# mcu.net
KiCad netlist of a schematic drawn in Altium Designer
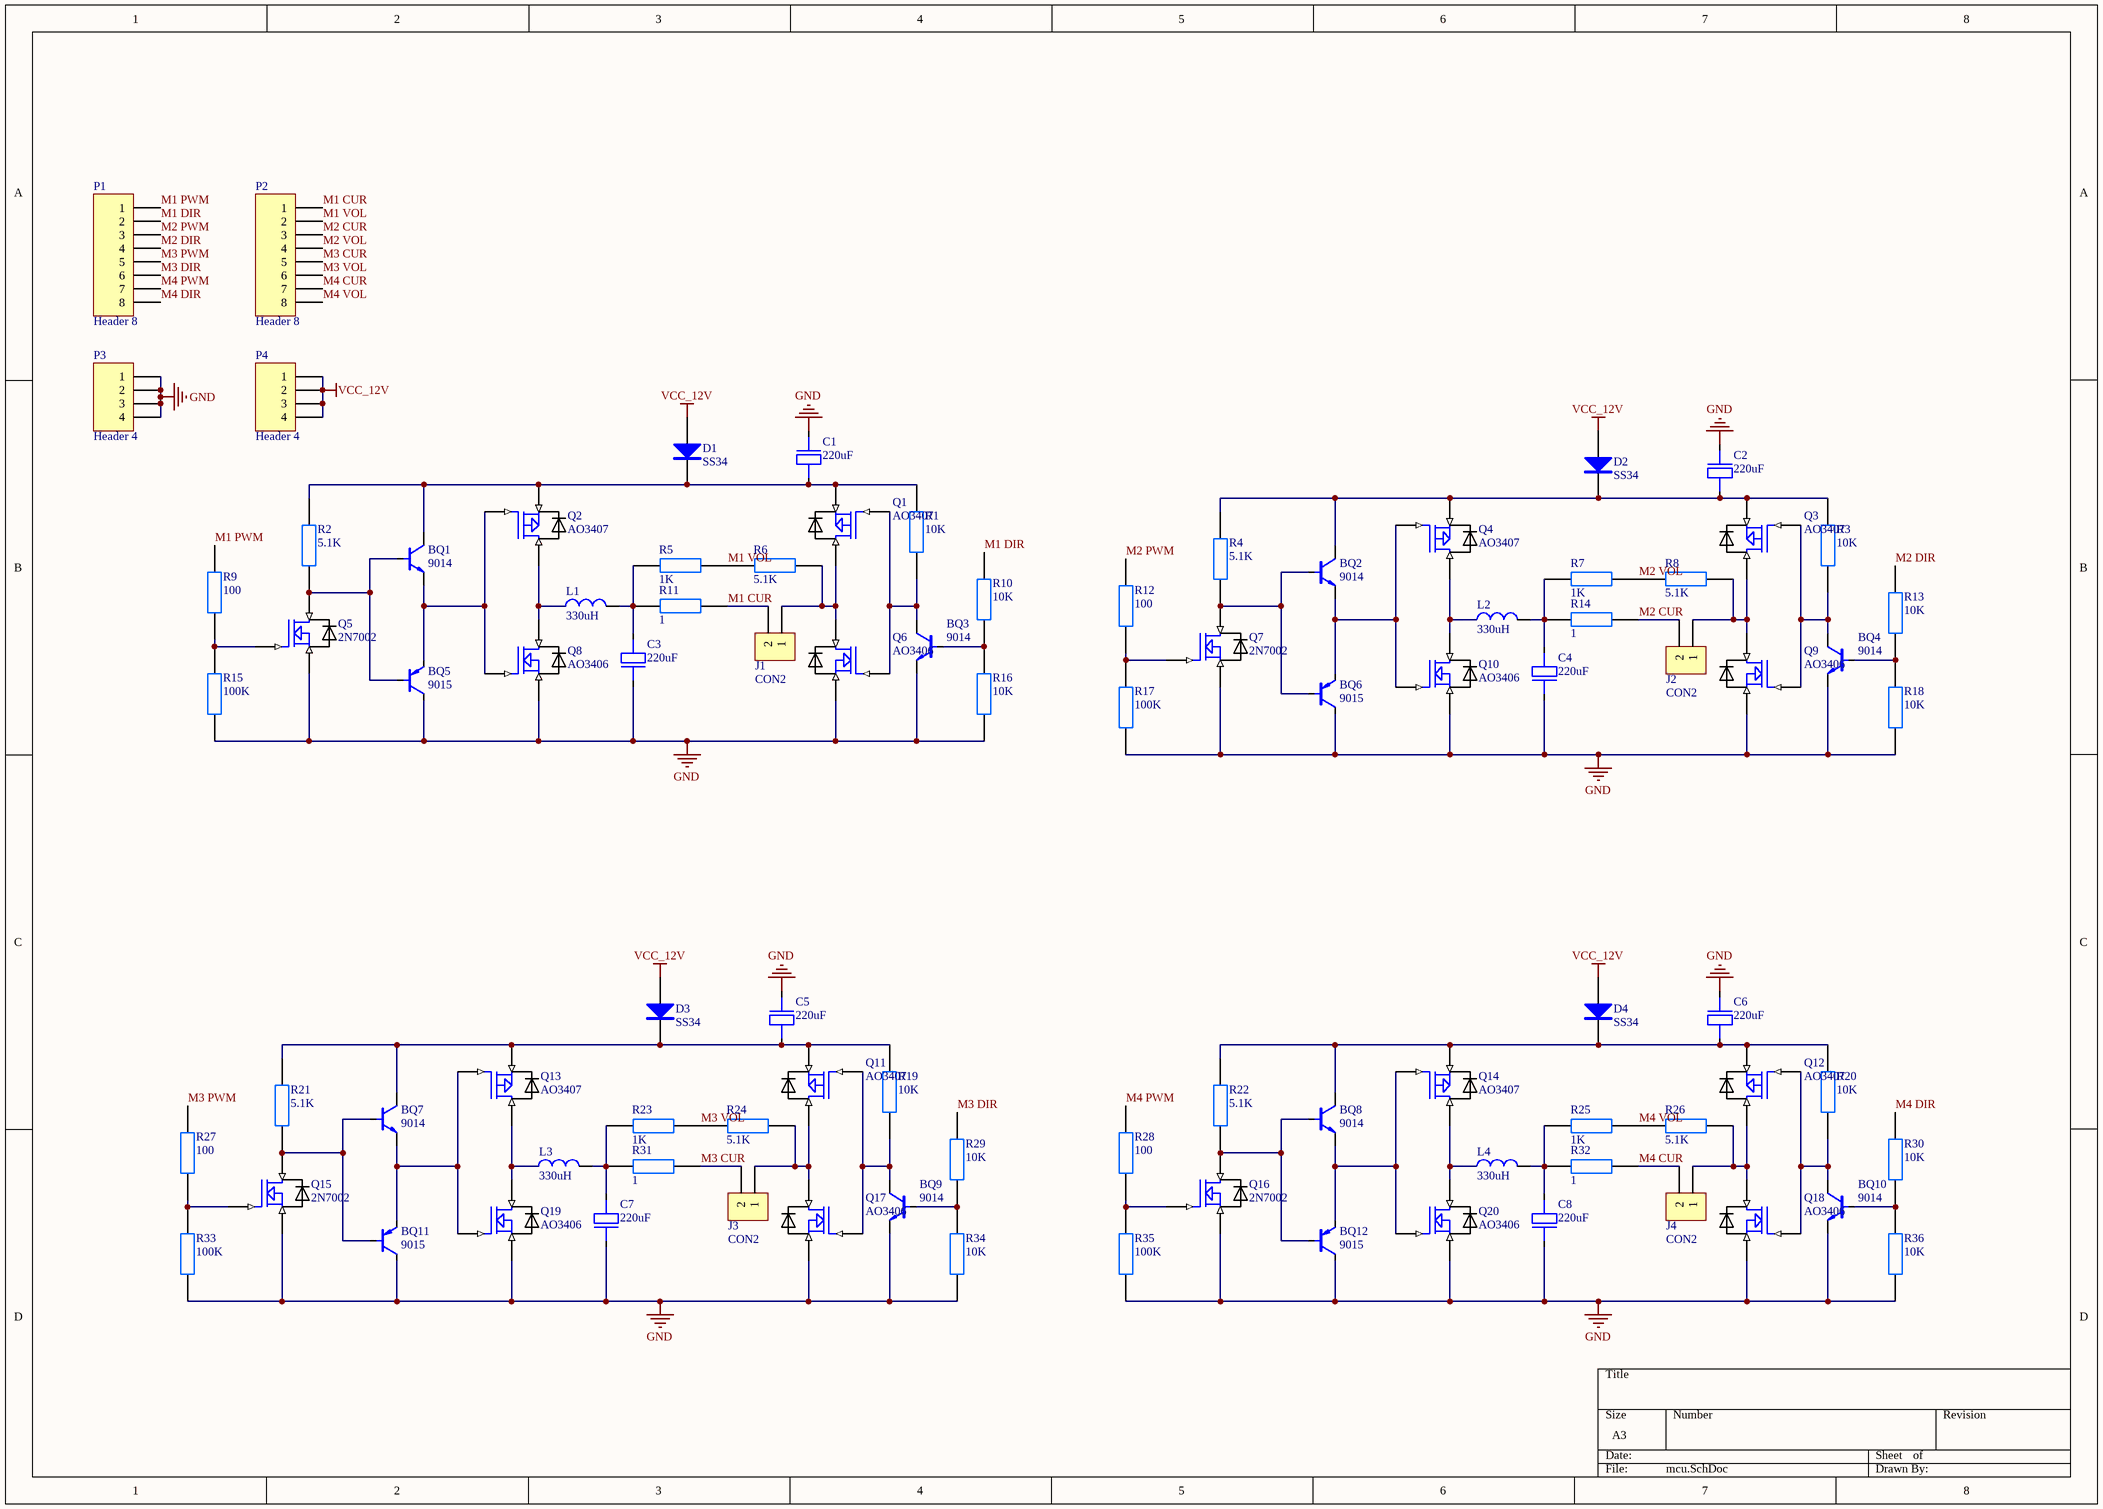
[diagram p0: mcu.SchDoc]

(export (version "E")
  (design (tool "Eeschema 10.0.6"))
  (components
    (comp (ref "BQ1")
      (value "9014")
      (footprint "SOT-23")
      (description "transistor")
      (libsource (lib "common") (part "9014"))
    )
    (comp (ref "BQ2")
      (value "9014")
      (footprint "SOT-23")
      (description "transistor")
      (libsource (lib "common") (part "9014"))
    )
    (comp (ref "BQ3")
      (value "9014")
      (footprint "SOT-23")
      (description "transistor")
      (libsource (lib "common") (part "9014"))
    )
    (comp (ref "BQ4")
      (value "9014")
      (footprint "SOT-23")
      (description "transistor")
      (libsource (lib "common") (part "9014"))
    )
    (comp (ref "BQ5")
      (value "9015")
      (footprint "SOT-23")
      (description "transistor")
      (libsource (lib "common") (part "9015"))
    )
    (comp (ref "BQ6")
      (value "9015")
      (footprint "SOT-23")
      (description "transistor")
      (libsource (lib "common") (part "9015"))
    )
    (comp (ref "BQ7")
      (value "9014")
      (footprint "SOT-23")
      (description "transistor")
      (libsource (lib "common") (part "9014"))
    )
    (comp (ref "BQ8")
      (value "9014")
      (footprint "SOT-23")
      (description "transistor")
      (libsource (lib "common") (part "9014"))
    )
    (comp (ref "BQ9")
      (value "9014")
      (footprint "SOT-23")
      (description "transistor")
      (libsource (lib "common") (part "9014"))
    )
    (comp (ref "BQ10")
      (value "9014")
      (footprint "SOT-23")
      (description "transistor")
      (libsource (lib "common") (part "9014"))
    )
    (comp (ref "BQ11")
      (value "9015")
      (footprint "SOT-23")
      (description "transistor")
      (libsource (lib "common") (part "9015"))
    )
    (comp (ref "BQ12")
      (value "9015")
      (footprint "SOT-23")
      (description "transistor")
      (libsource (lib "common") (part "9015"))
    )
    (comp (ref "C1") (value "220uF") (footprint "7443") (libsource (lib "common") (part "Electrolytic CAP")))
    (comp (ref "C2") (value "220uF") (footprint "7443") (libsource (lib "common") (part "Electrolytic CAP")))
    (comp (ref "C3") (value "220uF") (footprint "7443") (libsource (lib "common") (part "Electrolytic CAP")))
    (comp (ref "C4") (value "220uF") (footprint "7443") (libsource (lib "common") (part "Electrolytic CAP")))
    (comp (ref "C5") (value "220uF") (footprint "7443") (libsource (lib "common") (part "Electrolytic CAP")))
    (comp (ref "C6") (value "220uF") (footprint "7443") (libsource (lib "common") (part "Electrolytic CAP")))
    (comp (ref "C7") (value "220uF") (footprint "7443") (libsource (lib "common") (part "Electrolytic CAP")))
    (comp (ref "C8") (value "220uF") (footprint "7443") (libsource (lib "common") (part "Electrolytic CAP")))
    (comp (ref "D1")
      (value "SS34")
      (footprint "DO-241AC")
      (description "Diode")
      (libsource (lib "common") (part "SS14"))
    )
    (comp (ref "D2")
      (value "SS34")
      (footprint "DO-241AC")
      (description "Diode")
      (libsource (lib "common") (part "SS14"))
    )
    (comp (ref "D3")
      (value "SS34")
      (footprint "DO-241AC")
      (description "Diode")
      (libsource (lib "common") (part "SS14"))
    )
    (comp (ref "D4")
      (value "SS34")
      (footprint "DO-241AC")
      (description "Diode")
      (libsource (lib "common") (part "SS14"))
    )
    (comp (ref "J1") (value "CON2") (footprint "con2") (libsource (lib "common") (part "CON2")))
    (comp (ref "J2") (value "CON2") (footprint "con2") (libsource (lib "common") (part "CON2")))
    (comp (ref "J3") (value "CON2") (footprint "con2") (libsource (lib "common") (part "CON2")))
    (comp (ref "J4") (value "CON2") (footprint "con2") (libsource (lib "common") (part "CON2")))
    (comp (ref "L1") (value "330uH") (footprint "12x12") (libsource (lib "common") (part "Inductance")))
    (comp (ref "L2") (value "330uH") (footprint "12x12") (libsource (lib "common") (part "Inductance")))
    (comp (ref "L3") (value "330uH") (footprint "12x12") (libsource (lib "common") (part "Inductance")))
    (comp (ref "L4") (value "330uH") (footprint "12x12") (libsource (lib "common") (part "Inductance")))
    (comp (ref "P1")
      (value "Header 8")
      (footprint "sip8 N")
      (description "Header, 8-Pin")
      (fields (field (name "PUBLISHER") "Altium Limited"))
      (libsource (lib "Miscellaneous Connectors") (part "Header 8"))
    )
    (comp (ref "P2")
      (value "Header 8")
      (footprint "sip8 N")
      (description "Header, 8-Pin")
      (fields (field (name "PUBLISHER") "Altium Limited"))
      (libsource (lib "Miscellaneous Connectors") (part "Header 8"))
    )
    (comp (ref "P3")
      (value "Header 4")
      (footprint "sip4 N")
      (description "Header, 4-Pin")
      (fields (field (name "PUBLISHER") "Altium Limited"))
      (libsource (lib "Miscellaneous Connectors") (part "Header 4"))
    )
    (comp (ref "P4")
      (value "Header 4")
      (footprint "sip4 N")
      (description "Header, 4-Pin")
      (fields (field (name "PUBLISHER") "Altium Limited"))
      (libsource (lib "Miscellaneous Connectors") (part "Header 4"))
    )
    (comp (ref "Q1") (value "AO3407") (footprint "sot-23") (libsource (lib "common") (part "AO3407")))
    (comp (ref "Q2") (value "AO3407") (footprint "sot-23") (libsource (lib "common") (part "AO3407")))
    (comp (ref "Q3") (value "AO3407") (footprint "sot-23") (libsource (lib "common") (part "AO3407")))
    (comp (ref "Q4") (value "AO3407") (footprint "sot-23") (libsource (lib "common") (part "AO3407")))
    (comp (ref "Q5") (value "2N7002") (footprint "sot-23") (libsource (lib "common") (part "2N7002")))
    (comp (ref "Q6") (value "AO3406") (footprint "sot-23") (libsource (lib "common") (part "AO3406")))
    (comp (ref "Q7") (value "2N7002") (footprint "sot-23") (libsource (lib "common") (part "2N7002")))
    (comp (ref "Q8") (value "AO3406") (footprint "sot-23") (libsource (lib "common") (part "AO3406")))
    (comp (ref "Q9") (value "AO3406") (footprint "sot-23") (libsource (lib "common") (part "AO3406")))
    (comp (ref "Q10") (value "AO3406") (footprint "sot-23") (libsource (lib "common") (part "AO3406")))
    (comp (ref "Q11") (value "AO3407") (footprint "sot-23") (libsource (lib "common") (part "AO3407")))
    (comp (ref "Q12") (value "AO3407") (footprint "sot-23") (libsource (lib "common") (part "AO3407")))
    (comp (ref "Q13") (value "AO3407") (footprint "sot-23") (libsource (lib "common") (part "AO3407")))
    (comp (ref "Q14") (value "AO3407") (footprint "sot-23") (libsource (lib "common") (part "AO3407")))
    (comp (ref "Q15") (value "2N7002") (footprint "sot-23") (libsource (lib "common") (part "2N7002")))
    (comp (ref "Q16") (value "2N7002") (footprint "sot-23") (libsource (lib "common") (part "2N7002")))
    (comp (ref "Q17") (value "AO3406") (footprint "sot-23") (libsource (lib "common") (part "AO3406")))
    (comp (ref "Q18") (value "AO3406") (footprint "sot-23") (libsource (lib "common") (part "AO3406")))
    (comp (ref "Q19") (value "AO3406") (footprint "sot-23") (libsource (lib "common") (part "AO3406")))
    (comp (ref "Q20") (value "AO3406") (footprint "sot-23") (libsource (lib "common") (part "AO3406")))
    (comp (ref "R1")
      (value "10K")
      (footprint "0805")
      (description "RES")
      (libsource (lib "common") (part "RES"))
    )
    (comp (ref "R2")
      (value "5.1K")
      (footprint "0805")
      (description "RES")
      (libsource (lib "common") (part "RES"))
    )
    (comp (ref "R3")
      (value "10K")
      (footprint "0805")
      (description "RES")
      (libsource (lib "common") (part "RES"))
    )
    (comp (ref "R4")
      (value "5.1K")
      (footprint "0805")
      (description "RES")
      (libsource (lib "common") (part "RES"))
    )
    (comp (ref "R5")
      (value "1K")
      (footprint "0805")
      (description "RES")
      (libsource (lib "common") (part "RES"))
    )
    (comp (ref "R6")
      (value "5.1K")
      (footprint "0805")
      (description "RES")
      (libsource (lib "common") (part "RES"))
    )
    (comp (ref "R7")
      (value "1K")
      (footprint "0805")
      (description "RES")
      (libsource (lib "common") (part "RES"))
    )
    (comp (ref "R8")
      (value "5.1K")
      (footprint "0805")
      (description "RES")
      (libsource (lib "common") (part "RES"))
    )
    (comp (ref "R9")
      (value "100")
      (footprint "0805")
      (description "RES")
      (libsource (lib "common") (part "RES"))
    )
    (comp (ref "R10")
      (value "10K")
      (footprint "0805")
      (description "RES")
      (libsource (lib "common") (part "RES"))
    )
    (comp (ref "R11")
      (value "1")
      (footprint "2512")
      (description "RES")
      (libsource (lib "common") (part "RES"))
    )
    (comp (ref "R12")
      (value "100")
      (footprint "0805")
      (description "RES")
      (libsource (lib "common") (part "RES"))
    )
    (comp (ref "R13")
      (value "10K")
      (footprint "0805")
      (description "RES")
      (libsource (lib "common") (part "RES"))
    )
    (comp (ref "R14")
      (value "1")
      (footprint "2512")
      (description "RES")
      (libsource (lib "common") (part "RES"))
    )
    (comp (ref "R15")
      (value "100K")
      (footprint "0805")
      (description "RES")
      (libsource (lib "common") (part "RES"))
    )
    (comp (ref "R16")
      (value "10K")
      (footprint "0805")
      (description "RES")
      (libsource (lib "common") (part "RES"))
    )
    (comp (ref "R17")
      (value "100K")
      (footprint "0805")
      (description "RES")
      (libsource (lib "common") (part "RES"))
    )
    (comp (ref "R18")
      (value "10K")
      (footprint "0805")
      (description "RES")
      (libsource (lib "common") (part "RES"))
    )
    (comp (ref "R19")
      (value "10K")
      (footprint "0805")
      (description "RES")
      (libsource (lib "common") (part "RES"))
    )
    (comp (ref "R20")
      (value "10K")
      (footprint "0805")
      (description "RES")
      (libsource (lib "common") (part "RES"))
    )
    (comp (ref "R21")
      (value "5.1K")
      (footprint "0805")
      (description "RES")
      (libsource (lib "common") (part "RES"))
    )
    (comp (ref "R22")
      (value "5.1K")
      (footprint "0805")
      (description "RES")
      (libsource (lib "common") (part "RES"))
    )
    (comp (ref "R23")
      (value "1K")
      (footprint "0805")
      (description "RES")
      (libsource (lib "common") (part "RES"))
    )
    (comp (ref "R24")
      (value "5.1K")
      (footprint "0805")
      (description "RES")
      (libsource (lib "common") (part "RES"))
    )
    (comp (ref "R25")
      (value "1K")
      (footprint "0805")
      (description "RES")
      (libsource (lib "common") (part "RES"))
    )
    (comp (ref "R26")
      (value "5.1K")
      (footprint "0805")
      (description "RES")
      (libsource (lib "common") (part "RES"))
    )
    (comp (ref "R27")
      (value "100")
      (footprint "0805")
      (description "RES")
      (libsource (lib "common") (part "RES"))
    )
    (comp (ref "R28")
      (value "100")
      (footprint "0805")
      (description "RES")
      (libsource (lib "common") (part "RES"))
    )
    (comp (ref "R29")
      (value "10K")
      (footprint "0805")
      (description "RES")
      (libsource (lib "common") (part "RES"))
    )
    (comp (ref "R30")
      (value "10K")
      (footprint "0805")
      (description "RES")
      (libsource (lib "common") (part "RES"))
    )
    (comp (ref "R31")
      (value "1")
      (footprint "2512")
      (description "RES")
      (libsource (lib "common") (part "RES"))
    )
    (comp (ref "R32")
      (value "1")
      (footprint "2512")
      (description "RES")
      (libsource (lib "common") (part "RES"))
    )
    (comp (ref "R33")
      (value "100K")
      (footprint "0805")
      (description "RES")
      (libsource (lib "common") (part "RES"))
    )
    (comp (ref "R34")
      (value "10K")
      (footprint "0805")
      (description "RES")
      (libsource (lib "common") (part "RES"))
    )
    (comp (ref "R35")
      (value "100K")
      (footprint "0805")
      (description "RES")
      (libsource (lib "common") (part "RES"))
    )
    (comp (ref "R36")
      (value "10K")
      (footprint "0805")
      (description "RES")
      (libsource (lib "common") (part "RES"))
    )
  )
  (nets
    (net (code "1") (name "/M1 CUR") (class "Default")
      (node (ref "J1") (pin "2") (pinfunction "2_2") (pintype "passive"))
      (node (ref "P2") (pin "1") (pinfunction "1_1") (pintype "passive"))
      (node (ref "R11") (pin "2") (pinfunction "2_2") (pintype "passive"))
    )
    (net (code "2") (name "/M1 DIR") (class "Default")
      (node (ref "P1") (pin "2") (pinfunction "2_2") (pintype "passive"))
      (node (ref "R10") (pin "2") (pinfunction "2_2") (pintype "passive"))
    )
    (net (code "3") (name "/M1 PWM") (class "Default")
      (node (ref "P1") (pin "1") (pinfunction "1_1") (pintype "passive"))
      (node (ref "R9") (pin "2") (pinfunction "2_2") (pintype "passive"))
    )
    (net (code "4") (name "/M1 VOL") (class "Default")
      (node (ref "P2") (pin "2") (pinfunction "2_2") (pintype "passive"))
      (node (ref "R5") (pin "2") (pinfunction "2_2") (pintype "passive"))
      (node (ref "R6") (pin "1") (pinfunction "1_1") (pintype "passive"))
    )
    (net (code "5") (name "/M2 CUR") (class "Default")
      (node (ref "J2") (pin "2") (pinfunction "2_2") (pintype "passive"))
      (node (ref "P2") (pin "3") (pinfunction "3_3") (pintype "passive"))
      (node (ref "R14") (pin "2") (pinfunction "2_2") (pintype "passive"))
    )
    (net (code "6") (name "/M2 DIR") (class "Default")
      (node (ref "P1") (pin "4") (pinfunction "4_4") (pintype "passive"))
      (node (ref "R13") (pin "2") (pinfunction "2_2") (pintype "passive"))
    )
    (net (code "7") (name "/M2 PWM") (class "Default")
      (node (ref "P1") (pin "3") (pinfunction "3_3") (pintype "passive"))
      (node (ref "R12") (pin "2") (pinfunction "2_2") (pintype "passive"))
    )
    (net (code "8") (name "/M2 VOL") (class "Default")
      (node (ref "P2") (pin "4") (pinfunction "4_4") (pintype "passive"))
      (node (ref "R7") (pin "2") (pinfunction "2_2") (pintype "passive"))
      (node (ref "R8") (pin "1") (pinfunction "1_1") (pintype "passive"))
    )
    (net (code "9") (name "/M3 CUR") (class "Default")
      (node (ref "J3") (pin "2") (pinfunction "2_2") (pintype "passive"))
      (node (ref "P2") (pin "5") (pinfunction "5_5") (pintype "passive"))
      (node (ref "R31") (pin "2") (pinfunction "2_2") (pintype "passive"))
    )
    (net (code "10") (name "/M3 DIR") (class "Default")
      (node (ref "P1") (pin "6") (pinfunction "6_6") (pintype "passive"))
      (node (ref "R29") (pin "2") (pinfunction "2_2") (pintype "passive"))
    )
    (net (code "11") (name "/M3 PWM") (class "Default")
      (node (ref "P1") (pin "5") (pinfunction "5_5") (pintype "passive"))
      (node (ref "R27") (pin "2") (pinfunction "2_2") (pintype "passive"))
    )
    (net (code "12") (name "/M3 VOL") (class "Default")
      (node (ref "P2") (pin "6") (pinfunction "6_6") (pintype "passive"))
      (node (ref "R23") (pin "2") (pinfunction "2_2") (pintype "passive"))
      (node (ref "R24") (pin "1") (pinfunction "1_1") (pintype "passive"))
    )
    (net (code "13") (name "/M4 CUR") (class "Default")
      (node (ref "J4") (pin "2") (pinfunction "2_2") (pintype "passive"))
      (node (ref "P2") (pin "7") (pinfunction "7_7") (pintype "passive"))
      (node (ref "R32") (pin "2") (pinfunction "2_2") (pintype "passive"))
    )
    (net (code "14") (name "/M4 DIR") (class "Default")
      (node (ref "P1") (pin "8") (pinfunction "8_8") (pintype "passive"))
      (node (ref "R30") (pin "2") (pinfunction "2_2") (pintype "passive"))
    )
    (net (code "15") (name "/M4 PWM") (class "Default")
      (node (ref "P1") (pin "7") (pinfunction "7_7") (pintype "passive"))
      (node (ref "R28") (pin "2") (pinfunction "2_2") (pintype "passive"))
    )
    (net (code "16") (name "/M4 VOL") (class "Default")
      (node (ref "P2") (pin "8") (pinfunction "8_8") (pintype "passive"))
      (node (ref "R25") (pin "2") (pinfunction "2_2") (pintype "passive"))
      (node (ref "R26") (pin "1") (pinfunction "1_1") (pintype "passive"))
    )
    (net (code "17") (name "GND") (class "Default")
      (node (ref "BQ10") (pin "e") (pinfunction "e_e") (pintype "passive"))
      (node (ref "BQ11") (pin "c") (pinfunction "c_c") (pintype "passive"))
      (node (ref "BQ12") (pin "c") (pinfunction "c_c") (pintype "passive"))
      (node (ref "BQ3") (pin "e") (pinfunction "e_e") (pintype "passive"))
      (node (ref "BQ4") (pin "e") (pinfunction "e_e") (pintype "passive"))
      (node (ref "BQ5") (pin "c") (pinfunction "c_c") (pintype "passive"))
      (node (ref "BQ6") (pin "c") (pinfunction "c_c") (pintype "passive"))
      (node (ref "BQ9") (pin "e") (pinfunction "e_e") (pintype "passive"))
      (node (ref "C1") (pin "2") (pinfunction "2_2") (pintype "passive"))
      (node (ref "C2") (pin "2") (pinfunction "2_2") (pintype "passive"))
      (node (ref "C3") (pin "2") (pinfunction "2_2") (pintype "passive"))
      (node (ref "C4") (pin "2") (pinfunction "2_2") (pintype "passive"))
      (node (ref "C5") (pin "2") (pinfunction "2_2") (pintype "passive"))
      (node (ref "C6") (pin "2") (pinfunction "2_2") (pintype "passive"))
      (node (ref "C7") (pin "2") (pinfunction "2_2") (pintype "passive"))
      (node (ref "C8") (pin "2") (pinfunction "2_2") (pintype "passive"))
      (node (ref "P3") (pin "1") (pinfunction "1_1") (pintype "passive"))
      (node (ref "P3") (pin "2") (pinfunction "2_2") (pintype "passive"))
      (node (ref "P3") (pin "3") (pinfunction "3_3") (pintype "passive"))
      (node (ref "P3") (pin "4") (pinfunction "4_4") (pintype "passive"))
      (node (ref "Q10") (pin "3") (pinfunction "S_3") (pintype "input"))
      (node (ref "Q15") (pin "3") (pinfunction "S_3") (pintype "input"))
      (node (ref "Q16") (pin "3") (pinfunction "S_3") (pintype "input"))
      (node (ref "Q17") (pin "3") (pinfunction "S_3") (pintype "input"))
      (node (ref "Q18") (pin "3") (pinfunction "S_3") (pintype "input"))
      (node (ref "Q19") (pin "3") (pinfunction "S_3") (pintype "input"))
      (node (ref "Q20") (pin "3") (pinfunction "S_3") (pintype "input"))
      (node (ref "Q5") (pin "3") (pinfunction "S_3") (pintype "input"))
      (node (ref "Q6") (pin "3") (pinfunction "S_3") (pintype "input"))
      (node (ref "Q7") (pin "3") (pinfunction "S_3") (pintype "input"))
      (node (ref "Q8") (pin "3") (pinfunction "S_3") (pintype "input"))
      (node (ref "Q9") (pin "3") (pinfunction "S_3") (pintype "input"))
      (node (ref "R15") (pin "1") (pinfunction "1_1") (pintype "passive"))
      (node (ref "R16") (pin "1") (pinfunction "1_1") (pintype "passive"))
      (node (ref "R17") (pin "1") (pinfunction "1_1") (pintype "passive"))
      (node (ref "R18") (pin "1") (pinfunction "1_1") (pintype "passive"))
      (node (ref "R33") (pin "1") (pinfunction "1_1") (pintype "passive"))
      (node (ref "R34") (pin "1") (pinfunction "1_1") (pintype "passive"))
      (node (ref "R35") (pin "1") (pinfunction "1_1") (pintype "passive"))
      (node (ref "R36") (pin "1") (pinfunction "1_1") (pintype "passive"))
    )
    (net (code "18") (name "Net-(BQ3-Padb)") (class "Default")
      (node (ref "BQ3") (pin "b") (pinfunction "b_b") (pintype "passive"))
      (node (ref "R10") (pin "1") (pinfunction "1_1") (pintype "passive"))
      (node (ref "R16") (pin "2") (pinfunction "2_2") (pintype "passive"))
    )
    (net (code "19") (name "Net-(BQ4-Padb)") (class "Default")
      (node (ref "BQ4") (pin "b") (pinfunction "b_b") (pintype "passive"))
      (node (ref "R13") (pin "1") (pinfunction "1_1") (pintype "passive"))
      (node (ref "R18") (pin "2") (pinfunction "2_2") (pintype "passive"))
    )
    (net (code "20") (name "Net-(BQ9-Padb)") (class "Default")
      (node (ref "BQ9") (pin "b") (pinfunction "b_b") (pintype "passive"))
      (node (ref "R29") (pin "1") (pinfunction "1_1") (pintype "passive"))
      (node (ref "R34") (pin "2") (pinfunction "2_2") (pintype "passive"))
    )
    (net (code "21") (name "Net-(BQ10-Padb)") (class "Default")
      (node (ref "BQ10") (pin "b") (pinfunction "b_b") (pintype "passive"))
      (node (ref "R30") (pin "1") (pinfunction "1_1") (pintype "passive"))
      (node (ref "R36") (pin "2") (pinfunction "2_2") (pintype "passive"))
    )
    (net (code "22") (name "Net-(C3-Pad1)") (class "Default")
      (node (ref "C3") (pin "1") (pinfunction "1_1") (pintype "passive"))
      (node (ref "L1") (pin "1") (pinfunction "1_1") (pintype "passive"))
      (node (ref "R11") (pin "1") (pinfunction "1_1") (pintype "passive"))
      (node (ref "R5") (pin "1") (pinfunction "1_1") (pintype "passive"))
    )
    (net (code "23") (name "Net-(C4-Pad1)") (class "Default")
      (node (ref "C4") (pin "1") (pinfunction "1_1") (pintype "passive"))
      (node (ref "L2") (pin "1") (pinfunction "1_1") (pintype "passive"))
      (node (ref "R14") (pin "1") (pinfunction "1_1") (pintype "passive"))
      (node (ref "R7") (pin "1") (pinfunction "1_1") (pintype "passive"))
    )
    (net (code "24") (name "Net-(C7-Pad1)") (class "Default")
      (node (ref "C7") (pin "1") (pinfunction "1_1") (pintype "passive"))
      (node (ref "L3") (pin "1") (pinfunction "1_1") (pintype "passive"))
      (node (ref "R23") (pin "1") (pinfunction "1_1") (pintype "passive"))
      (node (ref "R31") (pin "1") (pinfunction "1_1") (pintype "passive"))
    )
    (net (code "25") (name "Net-(C8-Pad1)") (class "Default")
      (node (ref "C8") (pin "1") (pinfunction "1_1") (pintype "passive"))
      (node (ref "L4") (pin "1") (pinfunction "1_1") (pintype "passive"))
      (node (ref "R25") (pin "1") (pinfunction "1_1") (pintype "passive"))
      (node (ref "R32") (pin "1") (pinfunction "1_1") (pintype "passive"))
    )
    (net (code "26") (name "Net-(D1-K)") (class "Default")
      (node (ref "BQ1") (pin "c") (pinfunction "c_c") (pintype "passive"))
      (node (ref "C1") (pin "1") (pinfunction "1_1") (pintype "passive"))
      (node (ref "D1") (pin "2") (pinfunction "K_2") (pintype "passive"))
      (node (ref "Q1") (pin "3") (pinfunction "S_3") (pintype "input"))
      (node (ref "Q2") (pin "3") (pinfunction "S_3") (pintype "input"))
      (node (ref "R1") (pin "2") (pinfunction "2_2") (pintype "passive"))
      (node (ref "R2") (pin "2") (pinfunction "2_2") (pintype "passive"))
    )
    (net (code "27") (name "Net-(D2-K)") (class "Default")
      (node (ref "BQ2") (pin "c") (pinfunction "c_c") (pintype "passive"))
      (node (ref "C2") (pin "1") (pinfunction "1_1") (pintype "passive"))
      (node (ref "D2") (pin "2") (pinfunction "K_2") (pintype "passive"))
      (node (ref "Q3") (pin "3") (pinfunction "S_3") (pintype "input"))
      (node (ref "Q4") (pin "3") (pinfunction "S_3") (pintype "input"))
      (node (ref "R3") (pin "2") (pinfunction "2_2") (pintype "passive"))
      (node (ref "R4") (pin "2") (pinfunction "2_2") (pintype "passive"))
    )
    (net (code "28") (name "Net-(D3-K)") (class "Default")
      (node (ref "BQ7") (pin "c") (pinfunction "c_c") (pintype "passive"))
      (node (ref "C5") (pin "1") (pinfunction "1_1") (pintype "passive"))
      (node (ref "D3") (pin "2") (pinfunction "K_2") (pintype "passive"))
      (node (ref "Q11") (pin "3") (pinfunction "S_3") (pintype "input"))
      (node (ref "Q13") (pin "3") (pinfunction "S_3") (pintype "input"))
      (node (ref "R19") (pin "2") (pinfunction "2_2") (pintype "passive"))
      (node (ref "R21") (pin "2") (pinfunction "2_2") (pintype "passive"))
    )
    (net (code "29") (name "Net-(D4-K)") (class "Default")
      (node (ref "BQ8") (pin "c") (pinfunction "c_c") (pintype "passive"))
      (node (ref "C6") (pin "1") (pinfunction "1_1") (pintype "passive"))
      (node (ref "D4") (pin "2") (pinfunction "K_2") (pintype "passive"))
      (node (ref "Q12") (pin "3") (pinfunction "S_3") (pintype "input"))
      (node (ref "Q14") (pin "3") (pinfunction "S_3") (pintype "input"))
      (node (ref "R20") (pin "2") (pinfunction "2_2") (pintype "passive"))
      (node (ref "R22") (pin "2") (pinfunction "2_2") (pintype "passive"))
    )
    (net (code "30") (name "Net-(Q1-D)") (class "Default")
      (node (ref "J1") (pin "1") (pinfunction "1_1") (pintype "passive"))
      (node (ref "Q1") (pin "2") (pinfunction "D_2") (pintype "input"))
      (node (ref "Q6") (pin "2") (pinfunction "D_2") (pintype "input"))
      (node (ref "R6") (pin "2") (pinfunction "2_2") (pintype "passive"))
    )
    (net (code "31") (name "Net-(Q1-G)") (class "Default")
      (node (ref "BQ3") (pin "c") (pinfunction "c_c") (pintype "passive"))
      (node (ref "Q1") (pin "1") (pinfunction "G_1") (pintype "input"))
      (node (ref "Q6") (pin "1") (pinfunction "G_1") (pintype "input"))
      (node (ref "R1") (pin "1") (pinfunction "1_1") (pintype "passive"))
    )
    (net (code "32") (name "Net-(Q2-D)") (class "Default")
      (node (ref "L1") (pin "2") (pinfunction "2_2") (pintype "passive"))
      (node (ref "Q2") (pin "2") (pinfunction "D_2") (pintype "input"))
      (node (ref "Q8") (pin "2") (pinfunction "D_2") (pintype "input"))
    )
    (net (code "33") (name "Net-(Q2-G)") (class "Default")
      (node (ref "BQ1") (pin "e") (pinfunction "e_e") (pintype "passive"))
      (node (ref "BQ5") (pin "e") (pinfunction "e_e") (pintype "passive"))
      (node (ref "Q2") (pin "1") (pinfunction "G_1") (pintype "input"))
      (node (ref "Q8") (pin "1") (pinfunction "G_1") (pintype "input"))
    )
    (net (code "34") (name "Net-(Q3-D)") (class "Default")
      (node (ref "J2") (pin "1") (pinfunction "1_1") (pintype "passive"))
      (node (ref "Q3") (pin "2") (pinfunction "D_2") (pintype "input"))
      (node (ref "Q9") (pin "2") (pinfunction "D_2") (pintype "input"))
      (node (ref "R8") (pin "2") (pinfunction "2_2") (pintype "passive"))
    )
    (net (code "35") (name "Net-(Q3-G)") (class "Default")
      (node (ref "BQ4") (pin "c") (pinfunction "c_c") (pintype "passive"))
      (node (ref "Q3") (pin "1") (pinfunction "G_1") (pintype "input"))
      (node (ref "Q9") (pin "1") (pinfunction "G_1") (pintype "input"))
      (node (ref "R3") (pin "1") (pinfunction "1_1") (pintype "passive"))
    )
    (net (code "36") (name "Net-(Q5-D)") (class "Default")
      (node (ref "BQ1") (pin "b") (pinfunction "b_b") (pintype "passive"))
      (node (ref "BQ5") (pin "b") (pinfunction "b_b") (pintype "passive"))
      (node (ref "Q5") (pin "2") (pinfunction "D_2") (pintype "input"))
      (node (ref "R2") (pin "1") (pinfunction "1_1") (pintype "passive"))
    )
    (net (code "37") (name "Net-(Q5-G)") (class "Default")
      (node (ref "Q5") (pin "1") (pinfunction "G_1") (pintype "input"))
      (node (ref "R15") (pin "2") (pinfunction "2_2") (pintype "passive"))
      (node (ref "R9") (pin "1") (pinfunction "1_1") (pintype "passive"))
    )
    (net (code "38") (name "Net-(Q7-D)") (class "Default")
      (node (ref "BQ2") (pin "b") (pinfunction "b_b") (pintype "passive"))
      (node (ref "BQ6") (pin "b") (pinfunction "b_b") (pintype "passive"))
      (node (ref "Q7") (pin "2") (pinfunction "D_2") (pintype "input"))
      (node (ref "R4") (pin "1") (pinfunction "1_1") (pintype "passive"))
    )
    (net (code "39") (name "Net-(Q7-G)") (class "Default")
      (node (ref "Q7") (pin "1") (pinfunction "G_1") (pintype "input"))
      (node (ref "R12") (pin "1") (pinfunction "1_1") (pintype "passive"))
      (node (ref "R17") (pin "2") (pinfunction "2_2") (pintype "passive"))
    )
    (net (code "40") (name "Net-(Q10-D)") (class "Default")
      (node (ref "L2") (pin "2") (pinfunction "2_2") (pintype "passive"))
      (node (ref "Q10") (pin "2") (pinfunction "D_2") (pintype "input"))
      (node (ref "Q4") (pin "2") (pinfunction "D_2") (pintype "input"))
    )
    (net (code "41") (name "Net-(Q10-G)") (class "Default")
      (node (ref "BQ2") (pin "e") (pinfunction "e_e") (pintype "passive"))
      (node (ref "BQ6") (pin "e") (pinfunction "e_e") (pintype "passive"))
      (node (ref "Q10") (pin "1") (pinfunction "G_1") (pintype "input"))
      (node (ref "Q4") (pin "1") (pinfunction "G_1") (pintype "input"))
    )
    (net (code "42") (name "Net-(Q11-D)") (class "Default")
      (node (ref "J3") (pin "1") (pinfunction "1_1") (pintype "passive"))
      (node (ref "Q11") (pin "2") (pinfunction "D_2") (pintype "input"))
      (node (ref "Q17") (pin "2") (pinfunction "D_2") (pintype "input"))
      (node (ref "R24") (pin "2") (pinfunction "2_2") (pintype "passive"))
    )
    (net (code "43") (name "Net-(Q11-G)") (class "Default")
      (node (ref "BQ9") (pin "c") (pinfunction "c_c") (pintype "passive"))
      (node (ref "Q11") (pin "1") (pinfunction "G_1") (pintype "input"))
      (node (ref "Q17") (pin "1") (pinfunction "G_1") (pintype "input"))
      (node (ref "R19") (pin "1") (pinfunction "1_1") (pintype "passive"))
    )
    (net (code "44") (name "Net-(Q12-D)") (class "Default")
      (node (ref "J4") (pin "1") (pinfunction "1_1") (pintype "passive"))
      (node (ref "Q12") (pin "2") (pinfunction "D_2") (pintype "input"))
      (node (ref "Q18") (pin "2") (pinfunction "D_2") (pintype "input"))
      (node (ref "R26") (pin "2") (pinfunction "2_2") (pintype "passive"))
    )
    (net (code "45") (name "Net-(Q12-G)") (class "Default")
      (node (ref "BQ10") (pin "c") (pinfunction "c_c") (pintype "passive"))
      (node (ref "Q12") (pin "1") (pinfunction "G_1") (pintype "input"))
      (node (ref "Q18") (pin "1") (pinfunction "G_1") (pintype "input"))
      (node (ref "R20") (pin "1") (pinfunction "1_1") (pintype "passive"))
    )
    (net (code "46") (name "Net-(Q13-D)") (class "Default")
      (node (ref "L3") (pin "2") (pinfunction "2_2") (pintype "passive"))
      (node (ref "Q13") (pin "2") (pinfunction "D_2") (pintype "input"))
      (node (ref "Q19") (pin "2") (pinfunction "D_2") (pintype "input"))
    )
    (net (code "47") (name "Net-(Q13-G)") (class "Default")
      (node (ref "BQ11") (pin "e") (pinfunction "e_e") (pintype "passive"))
      (node (ref "BQ7") (pin "e") (pinfunction "e_e") (pintype "passive"))
      (node (ref "Q13") (pin "1") (pinfunction "G_1") (pintype "input"))
      (node (ref "Q19") (pin "1") (pinfunction "G_1") (pintype "input"))
    )
    (net (code "48") (name "Net-(Q14-D)") (class "Default")
      (node (ref "L4") (pin "2") (pinfunction "2_2") (pintype "passive"))
      (node (ref "Q14") (pin "2") (pinfunction "D_2") (pintype "input"))
      (node (ref "Q20") (pin "2") (pinfunction "D_2") (pintype "input"))
    )
    (net (code "49") (name "Net-(Q14-G)") (class "Default")
      (node (ref "BQ12") (pin "e") (pinfunction "e_e") (pintype "passive"))
      (node (ref "BQ8") (pin "e") (pinfunction "e_e") (pintype "passive"))
      (node (ref "Q14") (pin "1") (pinfunction "G_1") (pintype "input"))
      (node (ref "Q20") (pin "1") (pinfunction "G_1") (pintype "input"))
    )
    (net (code "50") (name "Net-(Q15-D)") (class "Default")
      (node (ref "BQ11") (pin "b") (pinfunction "b_b") (pintype "passive"))
      (node (ref "BQ7") (pin "b") (pinfunction "b_b") (pintype "passive"))
      (node (ref "Q15") (pin "2") (pinfunction "D_2") (pintype "input"))
      (node (ref "R21") (pin "1") (pinfunction "1_1") (pintype "passive"))
    )
    (net (code "51") (name "Net-(Q15-G)") (class "Default")
      (node (ref "Q15") (pin "1") (pinfunction "G_1") (pintype "input"))
      (node (ref "R27") (pin "1") (pinfunction "1_1") (pintype "passive"))
      (node (ref "R33") (pin "2") (pinfunction "2_2") (pintype "passive"))
    )
    (net (code "52") (name "Net-(Q16-D)") (class "Default")
      (node (ref "BQ12") (pin "b") (pinfunction "b_b") (pintype "passive"))
      (node (ref "BQ8") (pin "b") (pinfunction "b_b") (pintype "passive"))
      (node (ref "Q16") (pin "2") (pinfunction "D_2") (pintype "input"))
      (node (ref "R22") (pin "1") (pinfunction "1_1") (pintype "passive"))
    )
    (net (code "53") (name "Net-(Q16-G)") (class "Default")
      (node (ref "Q16") (pin "1") (pinfunction "G_1") (pintype "input"))
      (node (ref "R28") (pin "1") (pinfunction "1_1") (pintype "passive"))
      (node (ref "R35") (pin "2") (pinfunction "2_2") (pintype "passive"))
    )
    (net (code "54") (name "VCC_12V") (class "Default")
      (node (ref "D1") (pin "1") (pinfunction "A_1") (pintype "passive"))
      (node (ref "D2") (pin "1") (pinfunction "A_1") (pintype "passive"))
      (node (ref "D3") (pin "1") (pinfunction "A_1") (pintype "passive"))
      (node (ref "D4") (pin "1") (pinfunction "A_1") (pintype "passive"))
      (node (ref "P4") (pin "1") (pinfunction "1_1") (pintype "passive"))
      (node (ref "P4") (pin "2") (pinfunction "2_2") (pintype "passive"))
      (node (ref "P4") (pin "3") (pinfunction "3_3") (pintype "passive"))
      (node (ref "P4") (pin "4") (pinfunction "4_4") (pintype "passive"))
    )
  )
)
